# joystickDisplay.net
KiCad netlist of a schematic drawn in Altium Designer
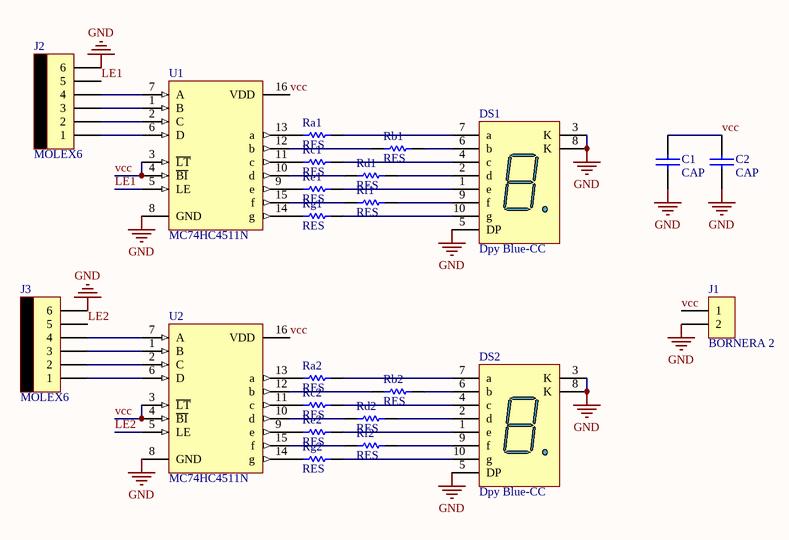
[diagram p0: joystickDisplay.SchDoc]

(export (version "E")
  (design (tool "Eeschema 10.0.6"))
  (components
    (comp (ref "C1") (value "CAP") (footprint "CAP200") (libsource (lib "LIBEBAL") (part "CAP")))
    (comp (ref "C2") (value "CAP") (footprint "CAP200") (libsource (lib "LIBEBAL") (part "CAP")))
    (comp (ref "DS1")
      (value "Dpy Blue-CC")
      (footprint "H")
      (description "14.2 mm General Purpose Blue 7-Segment Display: CC, RH DP, Gray Surface")
      (fields (field (name "PUBLISHER") "Altium Limited"))
      (libsource (lib "Miscellaneous Devices") (part "Dpy Blue-CC"))
    )
    (comp (ref "DS2")
      (value "Dpy Blue-CC")
      (footprint "H")
      (description "14.2 mm General Purpose Blue 7-Segment Display: CC, RH DP, Gray Surface")
      (fields (field (name "PUBLISHER") "Altium Limited"))
      (libsource (lib "Miscellaneous Devices") (part "Dpy Blue-CC"))
    )
    (comp (ref "J1")
      (value "BORNERA 2")
      (footprint "BORNERA2")
      (libsource (lib "LIBEBAL") (part "BORNERA 2"))
    )
    (comp (ref "J2") (value "MOLEX6") (footprint "MOLEX6") (libsource (lib "LIBEBAL") (part "MOLEX6")))
    (comp (ref "J3") (value "MOLEX6") (footprint "MOLEX6") (libsource (lib "LIBEBAL") (part "MOLEX6")))
    (comp (ref "Ra1") (value "RES") (footprint "RES400") (libsource (lib "LIBEBAL") (part "RES")))
    (comp (ref "Ra2") (value "RES") (footprint "RES400") (libsource (lib "LIBEBAL") (part "RES")))
    (comp (ref "Rb1") (value "RES") (footprint "RES400") (libsource (lib "LIBEBAL") (part "RES")))
    (comp (ref "Rb2") (value "RES") (footprint "RES400") (libsource (lib "LIBEBAL") (part "RES")))
    (comp (ref "Rc1") (value "RES") (footprint "RES400") (libsource (lib "LIBEBAL") (part "RES")))
    (comp (ref "Rc2") (value "RES") (footprint "RES400") (libsource (lib "LIBEBAL") (part "RES")))
    (comp (ref "Rd1") (value "RES") (footprint "RES400") (libsource (lib "LIBEBAL") (part "RES")))
    (comp (ref "Rd2") (value "RES") (footprint "RES400") (libsource (lib "LIBEBAL") (part "RES")))
    (comp (ref "Re1") (value "RES") (footprint "RES400") (libsource (lib "LIBEBAL") (part "RES")))
    (comp (ref "Re2") (value "RES") (footprint "RES400") (libsource (lib "LIBEBAL") (part "RES")))
    (comp (ref "Rf1") (value "RES") (footprint "RES400") (libsource (lib "LIBEBAL") (part "RES")))
    (comp (ref "Rf2") (value "RES") (footprint "RES400") (libsource (lib "LIBEBAL") (part "RES")))
    (comp (ref "Rg1") (value "RES") (footprint "RES400") (libsource (lib "LIBEBAL") (part "RES")))
    (comp (ref "Rg2") (value "RES") (footprint "RES400") (libsource (lib "LIBEBAL") (part "RES")))
    (comp (ref "U1")
      (value "MC74HC4511N")
      (footprint "648-08")
      (description "BCD-to-Seven-Segment Latch/Decoder/Display Driver")
      (fields (field (name "PUBLISHER") "Altium Limited"))
      (libsource (lib "Motorola Interface Display Driver") (part "MC74HC4511N"))
    )
    (comp (ref "U2")
      (value "MC74HC4511N")
      (footprint "648-08")
      (description "BCD-to-Seven-Segment Latch/Decoder/Display Driver")
      (fields (field (name "PUBLISHER") "Altium Limited"))
      (libsource (lib "Motorola Interface Display Driver") (part "MC74HC4511N"))
    )
  )
  (nets
    (net (code "1") (name "/LE1") (class "Default")
      (node (ref "J2") (pin "5") (pinfunction "5_5") (pintype "passive"))
      (node (ref "U1") (pin "5") (pinfunction "LE_5") (pintype "input"))
    )
    (net (code "2") (name "/LE2") (class "Default")
      (node (ref "J3") (pin "5") (pinfunction "5_5") (pintype "passive"))
      (node (ref "U2") (pin "5") (pinfunction "LE_5") (pintype "input"))
    )
    (net (code "3") (name "/vcc") (class "Default")
      (node (ref "C1") (pin "1") (pinfunction "1_1") (pintype "passive"))
      (node (ref "C2") (pin "1") (pinfunction "1_1") (pintype "passive"))
      (node (ref "J1") (pin "1") (pinfunction "1_1") (pintype "passive"))
      (node (ref "U1") (pin "16") (pinfunction "VDD_16") (pintype "power_in"))
      (node (ref "U1") (pin "3") (pinfunction "~{LT}_3") (pintype "input"))
      (node (ref "U1") (pin "4") (pinfunction "~{BI}_4") (pintype "input"))
      (node (ref "U2") (pin "16") (pinfunction "VDD_16") (pintype "power_in"))
      (node (ref "U2") (pin "3") (pinfunction "~{LT}_3") (pintype "input"))
      (node (ref "U2") (pin "4") (pinfunction "~{BI}_4") (pintype "input"))
    )
    (net (code "4") (name "GND") (class "Default")
      (node (ref "C1") (pin "2") (pinfunction "2_2") (pintype "passive"))
      (node (ref "C2") (pin "2") (pinfunction "2_2") (pintype "passive"))
      (node (ref "DS1") (pin "3") (pinfunction "K_3") (pintype "passive"))
      (node (ref "DS1") (pin "5") (pinfunction "DP_5") (pintype "passive"))
      (node (ref "DS1") (pin "8") (pinfunction "K_8") (pintype "passive"))
      (node (ref "DS2") (pin "3") (pinfunction "K_3") (pintype "passive"))
      (node (ref "DS2") (pin "5") (pinfunction "DP_5") (pintype "passive"))
      (node (ref "DS2") (pin "8") (pinfunction "K_8") (pintype "passive"))
      (node (ref "J1") (pin "2") (pinfunction "2_2") (pintype "passive"))
      (node (ref "J2") (pin "6") (pinfunction "6_6") (pintype "passive"))
      (node (ref "J3") (pin "6") (pinfunction "6_6") (pintype "passive"))
      (node (ref "U1") (pin "8") (pinfunction "GND_8") (pintype "power_in"))
      (node (ref "U2") (pin "8") (pinfunction "GND_8") (pintype "power_in"))
    )
    (net (code "5") (name "Net-(DS1-a)") (class "Default")
      (node (ref "DS1") (pin "7") (pinfunction "a_7") (pintype "passive"))
      (node (ref "Ra1") (pin "2") (pinfunction "2_2") (pintype "passive"))
    )
    (net (code "6") (name "Net-(DS1-b)") (class "Default")
      (node (ref "DS1") (pin "6") (pinfunction "b_6") (pintype "passive"))
      (node (ref "Rb1") (pin "2") (pinfunction "2_2") (pintype "passive"))
    )
    (net (code "7") (name "Net-(DS1-c)") (class "Default")
      (node (ref "DS1") (pin "4") (pinfunction "c_4") (pintype "passive"))
      (node (ref "Rc1") (pin "2") (pinfunction "2_2") (pintype "passive"))
    )
    (net (code "8") (name "Net-(DS1-d)") (class "Default")
      (node (ref "DS1") (pin "2") (pinfunction "d_2") (pintype "passive"))
      (node (ref "Rd1") (pin "2") (pinfunction "2_2") (pintype "passive"))
    )
    (net (code "9") (name "Net-(DS1-e)") (class "Default")
      (node (ref "DS1") (pin "1") (pinfunction "e_1") (pintype "passive"))
      (node (ref "Re1") (pin "2") (pinfunction "2_2") (pintype "passive"))
    )
    (net (code "10") (name "Net-(DS1-f)") (class "Default")
      (node (ref "DS1") (pin "9") (pinfunction "f_9") (pintype "passive"))
      (node (ref "Rf1") (pin "2") (pinfunction "2_2") (pintype "passive"))
    )
    (net (code "11") (name "Net-(DS1-g)") (class "Default")
      (node (ref "DS1") (pin "10") (pinfunction "g_10") (pintype "passive"))
      (node (ref "Rg1") (pin "2") (pinfunction "2_2") (pintype "passive"))
    )
    (net (code "12") (name "Net-(DS2-a)") (class "Default")
      (node (ref "DS2") (pin "7") (pinfunction "a_7") (pintype "passive"))
      (node (ref "Ra2") (pin "2") (pinfunction "2_2") (pintype "passive"))
    )
    (net (code "13") (name "Net-(DS2-b)") (class "Default")
      (node (ref "DS2") (pin "6") (pinfunction "b_6") (pintype "passive"))
      (node (ref "Rb2") (pin "2") (pinfunction "2_2") (pintype "passive"))
    )
    (net (code "14") (name "Net-(DS2-c)") (class "Default")
      (node (ref "DS2") (pin "4") (pinfunction "c_4") (pintype "passive"))
      (node (ref "Rc2") (pin "2") (pinfunction "2_2") (pintype "passive"))
    )
    (net (code "15") (name "Net-(DS2-d)") (class "Default")
      (node (ref "DS2") (pin "2") (pinfunction "d_2") (pintype "passive"))
      (node (ref "Rd2") (pin "2") (pinfunction "2_2") (pintype "passive"))
    )
    (net (code "16") (name "Net-(DS2-e)") (class "Default")
      (node (ref "DS2") (pin "1") (pinfunction "e_1") (pintype "passive"))
      (node (ref "Re2") (pin "2") (pinfunction "2_2") (pintype "passive"))
    )
    (net (code "17") (name "Net-(DS2-f)") (class "Default")
      (node (ref "DS2") (pin "9") (pinfunction "f_9") (pintype "passive"))
      (node (ref "Rf2") (pin "2") (pinfunction "2_2") (pintype "passive"))
    )
    (net (code "18") (name "Net-(DS2-g)") (class "Default")
      (node (ref "DS2") (pin "10") (pinfunction "g_10") (pintype "passive"))
      (node (ref "Rg2") (pin "2") (pinfunction "2_2") (pintype "passive"))
    )
    (net (code "19") (name "Net-(U1-A)") (class "Default")
      (node (ref "J2") (pin "4") (pinfunction "4_4") (pintype "passive"))
      (node (ref "U1") (pin "7") (pinfunction "A_7") (pintype "input"))
    )
    (net (code "20") (name "Net-(U1-B)") (class "Default")
      (node (ref "J2") (pin "3") (pinfunction "3_3") (pintype "passive"))
      (node (ref "U1") (pin "1") (pinfunction "B_1") (pintype "input"))
    )
    (net (code "21") (name "Net-(U1-C)") (class "Default")
      (node (ref "J2") (pin "2") (pinfunction "2_2") (pintype "passive"))
      (node (ref "U1") (pin "2") (pinfunction "C_2") (pintype "input"))
    )
    (net (code "22") (name "Net-(U1-D)") (class "Default")
      (node (ref "J2") (pin "1") (pinfunction "1_1") (pintype "passive"))
      (node (ref "U1") (pin "6") (pinfunction "D_6") (pintype "input"))
    )
    (net (code "23") (name "Net-(U1-a)") (class "Default")
      (node (ref "Ra1") (pin "1") (pinfunction "1_1") (pintype "passive"))
      (node (ref "U1") (pin "13") (pinfunction "a_13") (pintype "output"))
    )
    (net (code "24") (name "Net-(U1-b)") (class "Default")
      (node (ref "Rb1") (pin "1") (pinfunction "1_1") (pintype "passive"))
      (node (ref "U1") (pin "12") (pinfunction "b_12") (pintype "output"))
    )
    (net (code "25") (name "Net-(U1-c)") (class "Default")
      (node (ref "Rc1") (pin "1") (pinfunction "1_1") (pintype "passive"))
      (node (ref "U1") (pin "11") (pinfunction "c_11") (pintype "output"))
    )
    (net (code "26") (name "Net-(U1-d)") (class "Default")
      (node (ref "Rd1") (pin "1") (pinfunction "1_1") (pintype "passive"))
      (node (ref "U1") (pin "10") (pinfunction "d_10") (pintype "output"))
    )
    (net (code "27") (name "Net-(U1-e)") (class "Default")
      (node (ref "Re1") (pin "1") (pinfunction "1_1") (pintype "passive"))
      (node (ref "U1") (pin "9") (pinfunction "e_9") (pintype "output"))
    )
    (net (code "28") (name "Net-(U1-f)") (class "Default")
      (node (ref "Rf1") (pin "1") (pinfunction "1_1") (pintype "passive"))
      (node (ref "U1") (pin "15") (pinfunction "f_15") (pintype "output"))
    )
    (net (code "29") (name "Net-(U1-g)") (class "Default")
      (node (ref "Rg1") (pin "1") (pinfunction "1_1") (pintype "passive"))
      (node (ref "U1") (pin "14") (pinfunction "g_14") (pintype "output"))
    )
    (net (code "30") (name "Net-(U2-A)") (class "Default")
      (node (ref "J3") (pin "4") (pinfunction "4_4") (pintype "passive"))
      (node (ref "U2") (pin "7") (pinfunction "A_7") (pintype "input"))
    )
    (net (code "31") (name "Net-(U2-B)") (class "Default")
      (node (ref "J3") (pin "3") (pinfunction "3_3") (pintype "passive"))
      (node (ref "U2") (pin "1") (pinfunction "B_1") (pintype "input"))
    )
    (net (code "32") (name "Net-(U2-C)") (class "Default")
      (node (ref "J3") (pin "2") (pinfunction "2_2") (pintype "passive"))
      (node (ref "U2") (pin "2") (pinfunction "C_2") (pintype "input"))
    )
    (net (code "33") (name "Net-(U2-D)") (class "Default")
      (node (ref "J3") (pin "1") (pinfunction "1_1") (pintype "passive"))
      (node (ref "U2") (pin "6") (pinfunction "D_6") (pintype "input"))
    )
    (net (code "34") (name "Net-(U2-a)") (class "Default")
      (node (ref "Ra2") (pin "1") (pinfunction "1_1") (pintype "passive"))
      (node (ref "U2") (pin "13") (pinfunction "a_13") (pintype "output"))
    )
    (net (code "35") (name "Net-(U2-b)") (class "Default")
      (node (ref "Rb2") (pin "1") (pinfunction "1_1") (pintype "passive"))
      (node (ref "U2") (pin "12") (pinfunction "b_12") (pintype "output"))
    )
    (net (code "36") (name "Net-(U2-c)") (class "Default")
      (node (ref "Rc2") (pin "1") (pinfunction "1_1") (pintype "passive"))
      (node (ref "U2") (pin "11") (pinfunction "c_11") (pintype "output"))
    )
    (net (code "37") (name "Net-(U2-d)") (class "Default")
      (node (ref "Rd2") (pin "1") (pinfunction "1_1") (pintype "passive"))
      (node (ref "U2") (pin "10") (pinfunction "d_10") (pintype "output"))
    )
    (net (code "38") (name "Net-(U2-e)") (class "Default")
      (node (ref "Re2") (pin "1") (pinfunction "1_1") (pintype "passive"))
      (node (ref "U2") (pin "9") (pinfunction "e_9") (pintype "output"))
    )
    (net (code "39") (name "Net-(U2-f)") (class "Default")
      (node (ref "Rf2") (pin "1") (pinfunction "1_1") (pintype "passive"))
      (node (ref "U2") (pin "15") (pinfunction "f_15") (pintype "output"))
    )
    (net (code "40") (name "Net-(U2-g)") (class "Default")
      (node (ref "Rg2") (pin "1") (pinfunction "1_1") (pintype "passive"))
      (node (ref "U2") (pin "14") (pinfunction "g_14") (pintype "output"))
    )
  )
)
